# 10_header.net
KiCad netlist of a schematic drawn in Altium Designer
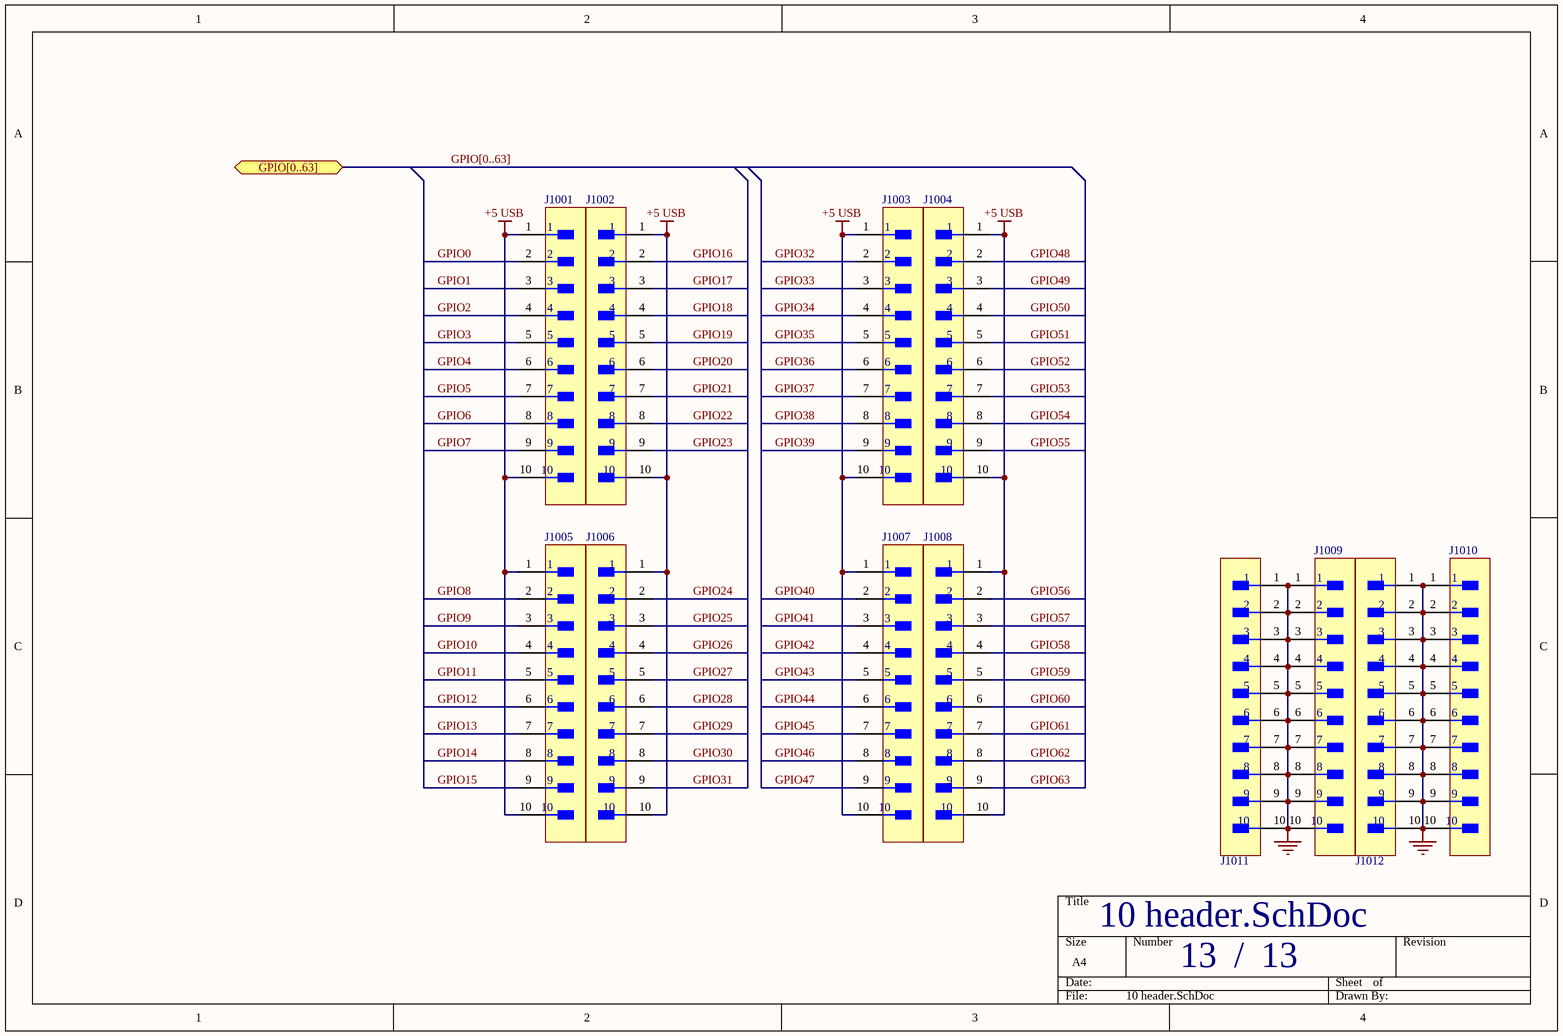
[diagram p0: 10 header.SchDoc]

(export (version "E")
  (design (tool "Eeschema 10.0.6"))
  (components
    (comp (ref "J1001")
      (value "TSW-110-07-T-S")
      (footprint "FP-TSW-110-07-T-S-MFG")
      (description "TSW-110-07-T-S TSW - Samtec 2.54mm Pin Header 10.92mm Overall Pin Length (07) (mcv)(TO22)")
      (libsource (lib "Altium Content Vault") (part "TSW-110-07-T-S"))
    )
    (comp (ref "J1002")
      (value "TSW-110-07-T-S")
      (footprint "FP-TSW-110-07-T-S-MFG")
      (description "TSW-110-07-T-S TSW - Samtec 2.54mm Pin Header 10.92mm Overall Pin Length (07) (mcv)(TO22)")
      (libsource (lib "") (part "TSW-110-07-T-S_1"))
    )
    (comp (ref "J1003")
      (value "TSW-110-07-T-S")
      (footprint "FP-TSW-110-07-T-S-MFG")
      (description "TSW-110-07-T-S TSW - Samtec 2.54mm Pin Header 10.92mm Overall Pin Length (07) (mcv)(TO22)")
      (libsource (lib "Altium Content Vault") (part "TSW-110-07-T-S"))
    )
    (comp (ref "J1004")
      (value "TSW-110-07-T-S")
      (footprint "FP-TSW-110-07-T-S-MFG")
      (description "TSW-110-07-T-S TSW - Samtec 2.54mm Pin Header 10.92mm Overall Pin Length (07) (mcv)(TO22)")
      (libsource (lib "") (part "TSW-110-07-T-S_1"))
    )
    (comp (ref "J1005")
      (value "TSW-110-07-T-S")
      (footprint "FP-TSW-110-07-T-S-MFG")
      (description "TSW-110-07-T-S TSW - Samtec 2.54mm Pin Header 10.92mm Overall Pin Length (07) (mcv)(TO22)")
      (libsource (lib "Altium Content Vault") (part "TSW-110-07-T-S"))
    )
    (comp (ref "J1006")
      (value "TSW-110-07-T-S")
      (footprint "FP-TSW-110-07-T-S-MFG")
      (description "TSW-110-07-T-S TSW - Samtec 2.54mm Pin Header 10.92mm Overall Pin Length (07) (mcv)(TO22)")
      (libsource (lib "") (part "TSW-110-07-T-S_1"))
    )
    (comp (ref "J1007")
      (value "TSW-110-07-T-S")
      (footprint "FP-TSW-110-07-T-S-MFG")
      (description "TSW-110-07-T-S TSW - Samtec 2.54mm Pin Header 10.92mm Overall Pin Length (07) (mcv)(TO22)")
      (libsource (lib "Altium Content Vault") (part "TSW-110-07-T-S"))
    )
    (comp (ref "J1008")
      (value "TSW-110-07-T-S")
      (footprint "FP-TSW-110-07-T-S-MFG")
      (description "TSW-110-07-T-S TSW - Samtec 2.54mm Pin Header 10.92mm Overall Pin Length (07) (mcv)(TO22)")
      (libsource (lib "") (part "TSW-110-07-T-S_1"))
    )
    (comp (ref "J1009")
      (value "TSW-110-07-T-S")
      (footprint "FP-TSW-110-07-T-S-MFG")
      (description "TSW-110-07-T-S TSW - Samtec 2.54mm Pin Header 10.92mm Overall Pin Length (07) (mcv)(TO22)")
      (libsource (lib "Altium Content Vault") (part "TSW-110-07-T-S"))
    )
    (comp (ref "J1010")
      (value "TSW-110-07-T-S")
      (footprint "FP-TSW-110-07-T-S-MFG")
      (description "TSW-110-07-T-S TSW - Samtec 2.54mm Pin Header 10.92mm Overall Pin Length (07) (mcv)(TO22)")
      (libsource (lib "Altium Content Vault") (part "TSW-110-07-T-S"))
    )
    (comp (ref "J1011")
      (value "TSW-110-07-T-S")
      (footprint "FP-TSW-110-07-T-S-MFG")
      (description "TSW-110-07-T-S TSW - Samtec 2.54mm Pin Header 10.92mm Overall Pin Length (07) (mcv)(TO22)")
      (libsource (lib "") (part "TSW-110-07-T-S_1"))
    )
    (comp (ref "J1012")
      (value "TSW-110-07-T-S")
      (footprint "FP-TSW-110-07-T-S-MFG")
      (description "TSW-110-07-T-S TSW - Samtec 2.54mm Pin Header 10.92mm Overall Pin Length (07) (mcv)(TO22)")
      (libsource (lib "") (part "TSW-110-07-T-S_1"))
    )
  )
  (nets
    (net (code "1") (name "+5 USB") (class "Default")
      (node (ref "J1001") (pin "1") (pinfunction "1_1") (pintype "passive"))
      (node (ref "J1001") (pin "10") (pinfunction "10_10") (pintype "passive"))
      (node (ref "J1002") (pin "1") (pinfunction "1_1") (pintype "passive"))
      (node (ref "J1002") (pin "10") (pinfunction "10_10") (pintype "passive"))
      (node (ref "J1003") (pin "1") (pinfunction "1_1") (pintype "passive"))
      (node (ref "J1003") (pin "10") (pinfunction "10_10") (pintype "passive"))
      (node (ref "J1004") (pin "1") (pinfunction "1_1") (pintype "passive"))
      (node (ref "J1004") (pin "10") (pinfunction "10_10") (pintype "passive"))
      (node (ref "J1005") (pin "1") (pinfunction "1_1") (pintype "passive"))
      (node (ref "J1005") (pin "10") (pinfunction "10_10") (pintype "passive"))
      (node (ref "J1006") (pin "1") (pinfunction "1_1") (pintype "passive"))
      (node (ref "J1006") (pin "10") (pinfunction "10_10") (pintype "passive"))
      (node (ref "J1007") (pin "1") (pinfunction "1_1") (pintype "passive"))
      (node (ref "J1007") (pin "10") (pinfunction "10_10") (pintype "passive"))
      (node (ref "J1008") (pin "1") (pinfunction "1_1") (pintype "passive"))
      (node (ref "J1008") (pin "10") (pinfunction "10_10") (pintype "passive"))
    )
    (net (code "2") (name "/GPIO0") (class "Default")
      (node (ref "J1001") (pin "2") (pinfunction "2_2") (pintype "passive"))
    )
    (net (code "3") (name "/GPIO1") (class "Default")
      (node (ref "J1001") (pin "3") (pinfunction "3_3") (pintype "passive"))
    )
    (net (code "4") (name "/GPIO2") (class "Default")
      (node (ref "J1001") (pin "4") (pinfunction "4_4") (pintype "passive"))
    )
    (net (code "5") (name "/GPIO3") (class "Default")
      (node (ref "J1001") (pin "5") (pinfunction "5_5") (pintype "passive"))
    )
    (net (code "6") (name "/GPIO4") (class "Default")
      (node (ref "J1001") (pin "6") (pinfunction "6_6") (pintype "passive"))
    )
    (net (code "7") (name "/GPIO5") (class "Default")
      (node (ref "J1001") (pin "7") (pinfunction "7_7") (pintype "passive"))
    )
    (net (code "8") (name "/GPIO6") (class "Default")
      (node (ref "J1001") (pin "8") (pinfunction "8_8") (pintype "passive"))
    )
    (net (code "9") (name "/GPIO7") (class "Default")
      (node (ref "J1001") (pin "9") (pinfunction "9_9") (pintype "passive"))
    )
    (net (code "10") (name "/GPIO8") (class "Default")
      (node (ref "J1005") (pin "2") (pinfunction "2_2") (pintype "passive"))
    )
    (net (code "11") (name "/GPIO9") (class "Default")
      (node (ref "J1005") (pin "3") (pinfunction "3_3") (pintype "passive"))
    )
    (net (code "12") (name "/GPIO10") (class "Default")
      (node (ref "J1005") (pin "4") (pinfunction "4_4") (pintype "passive"))
    )
    (net (code "13") (name "/GPIO11") (class "Default")
      (node (ref "J1005") (pin "5") (pinfunction "5_5") (pintype "passive"))
    )
    (net (code "14") (name "/GPIO12") (class "Default")
      (node (ref "J1005") (pin "6") (pinfunction "6_6") (pintype "passive"))
    )
    (net (code "15") (name "/GPIO13") (class "Default")
      (node (ref "J1005") (pin "7") (pinfunction "7_7") (pintype "passive"))
    )
    (net (code "16") (name "/GPIO14") (class "Default")
      (node (ref "J1005") (pin "8") (pinfunction "8_8") (pintype "passive"))
    )
    (net (code "17") (name "/GPIO15") (class "Default")
      (node (ref "J1005") (pin "9") (pinfunction "9_9") (pintype "passive"))
    )
    (net (code "18") (name "/GPIO16") (class "Default")
      (node (ref "J1002") (pin "2") (pinfunction "2_2") (pintype "passive"))
    )
    (net (code "19") (name "/GPIO17") (class "Default")
      (node (ref "J1002") (pin "3") (pinfunction "3_3") (pintype "passive"))
    )
    (net (code "20") (name "/GPIO18") (class "Default")
      (node (ref "J1002") (pin "4") (pinfunction "4_4") (pintype "passive"))
    )
    (net (code "21") (name "/GPIO19") (class "Default")
      (node (ref "J1002") (pin "5") (pinfunction "5_5") (pintype "passive"))
    )
    (net (code "22") (name "/GPIO20") (class "Default")
      (node (ref "J1002") (pin "6") (pinfunction "6_6") (pintype "passive"))
    )
    (net (code "23") (name "/GPIO21") (class "Default")
      (node (ref "J1002") (pin "7") (pinfunction "7_7") (pintype "passive"))
    )
    (net (code "24") (name "/GPIO22") (class "Default")
      (node (ref "J1002") (pin "8") (pinfunction "8_8") (pintype "passive"))
    )
    (net (code "25") (name "/GPIO23") (class "Default")
      (node (ref "J1002") (pin "9") (pinfunction "9_9") (pintype "passive"))
    )
    (net (code "26") (name "/GPIO24") (class "Default")
      (node (ref "J1006") (pin "2") (pinfunction "2_2") (pintype "passive"))
    )
    (net (code "27") (name "/GPIO25") (class "Default")
      (node (ref "J1006") (pin "3") (pinfunction "3_3") (pintype "passive"))
    )
    (net (code "28") (name "/GPIO26") (class "Default")
      (node (ref "J1006") (pin "4") (pinfunction "4_4") (pintype "passive"))
    )
    (net (code "29") (name "/GPIO27") (class "Default")
      (node (ref "J1006") (pin "5") (pinfunction "5_5") (pintype "passive"))
    )
    (net (code "30") (name "/GPIO28") (class "Default")
      (node (ref "J1006") (pin "6") (pinfunction "6_6") (pintype "passive"))
    )
    (net (code "31") (name "/GPIO29") (class "Default")
      (node (ref "J1006") (pin "7") (pinfunction "7_7") (pintype "passive"))
    )
    (net (code "32") (name "/GPIO30") (class "Default")
      (node (ref "J1006") (pin "8") (pinfunction "8_8") (pintype "passive"))
    )
    (net (code "33") (name "/GPIO31") (class "Default")
      (node (ref "J1006") (pin "9") (pinfunction "9_9") (pintype "passive"))
    )
    (net (code "34") (name "/GPIO32") (class "Default")
      (node (ref "J1003") (pin "2") (pinfunction "2_2") (pintype "passive"))
    )
    (net (code "35") (name "/GPIO33") (class "Default")
      (node (ref "J1003") (pin "3") (pinfunction "3_3") (pintype "passive"))
    )
    (net (code "36") (name "/GPIO34") (class "Default")
      (node (ref "J1003") (pin "4") (pinfunction "4_4") (pintype "passive"))
    )
    (net (code "37") (name "/GPIO35") (class "Default")
      (node (ref "J1003") (pin "5") (pinfunction "5_5") (pintype "passive"))
    )
    (net (code "38") (name "/GPIO36") (class "Default")
      (node (ref "J1003") (pin "6") (pinfunction "6_6") (pintype "passive"))
    )
    (net (code "39") (name "/GPIO37") (class "Default")
      (node (ref "J1003") (pin "7") (pinfunction "7_7") (pintype "passive"))
    )
    (net (code "40") (name "/GPIO38") (class "Default")
      (node (ref "J1003") (pin "8") (pinfunction "8_8") (pintype "passive"))
    )
    (net (code "41") (name "/GPIO39") (class "Default")
      (node (ref "J1003") (pin "9") (pinfunction "9_9") (pintype "passive"))
    )
    (net (code "42") (name "/GPIO40") (class "Default")
      (node (ref "J1007") (pin "2") (pinfunction "2_2") (pintype "passive"))
    )
    (net (code "43") (name "/GPIO41") (class "Default")
      (node (ref "J1007") (pin "3") (pinfunction "3_3") (pintype "passive"))
    )
    (net (code "44") (name "/GPIO42") (class "Default")
      (node (ref "J1007") (pin "4") (pinfunction "4_4") (pintype "passive"))
    )
    (net (code "45") (name "/GPIO43") (class "Default")
      (node (ref "J1007") (pin "5") (pinfunction "5_5") (pintype "passive"))
    )
    (net (code "46") (name "/GPIO44") (class "Default")
      (node (ref "J1007") (pin "6") (pinfunction "6_6") (pintype "passive"))
    )
    (net (code "47") (name "/GPIO45") (class "Default")
      (node (ref "J1007") (pin "7") (pinfunction "7_7") (pintype "passive"))
    )
    (net (code "48") (name "/GPIO46") (class "Default")
      (node (ref "J1007") (pin "8") (pinfunction "8_8") (pintype "passive"))
    )
    (net (code "49") (name "/GPIO47") (class "Default")
      (node (ref "J1007") (pin "9") (pinfunction "9_9") (pintype "passive"))
    )
    (net (code "50") (name "/GPIO48") (class "Default")
      (node (ref "J1004") (pin "2") (pinfunction "2_2") (pintype "passive"))
    )
    (net (code "51") (name "/GPIO49") (class "Default")
      (node (ref "J1004") (pin "3") (pinfunction "3_3") (pintype "passive"))
    )
    (net (code "52") (name "/GPIO50") (class "Default")
      (node (ref "J1004") (pin "4") (pinfunction "4_4") (pintype "passive"))
    )
    (net (code "53") (name "/GPIO51") (class "Default")
      (node (ref "J1004") (pin "5") (pinfunction "5_5") (pintype "passive"))
    )
    (net (code "54") (name "/GPIO52") (class "Default")
      (node (ref "J1004") (pin "6") (pinfunction "6_6") (pintype "passive"))
    )
    (net (code "55") (name "/GPIO53") (class "Default")
      (node (ref "J1004") (pin "7") (pinfunction "7_7") (pintype "passive"))
    )
    (net (code "56") (name "/GPIO54") (class "Default")
      (node (ref "J1004") (pin "8") (pinfunction "8_8") (pintype "passive"))
    )
    (net (code "57") (name "/GPIO55") (class "Default")
      (node (ref "J1004") (pin "9") (pinfunction "9_9") (pintype "passive"))
    )
    (net (code "58") (name "/GPIO56") (class "Default")
      (node (ref "J1008") (pin "2") (pinfunction "2_2") (pintype "passive"))
    )
    (net (code "59") (name "/GPIO57") (class "Default")
      (node (ref "J1008") (pin "3") (pinfunction "3_3") (pintype "passive"))
    )
    (net (code "60") (name "/GPIO58") (class "Default")
      (node (ref "J1008") (pin "4") (pinfunction "4_4") (pintype "passive"))
    )
    (net (code "61") (name "/GPIO59") (class "Default")
      (node (ref "J1008") (pin "5") (pinfunction "5_5") (pintype "passive"))
    )
    (net (code "62") (name "/GPIO60") (class "Default")
      (node (ref "J1008") (pin "6") (pinfunction "6_6") (pintype "passive"))
    )
    (net (code "63") (name "/GPIO61") (class "Default")
      (node (ref "J1008") (pin "7") (pinfunction "7_7") (pintype "passive"))
    )
    (net (code "64") (name "/GPIO62") (class "Default")
      (node (ref "J1008") (pin "8") (pinfunction "8_8") (pintype "passive"))
    )
    (net (code "65") (name "/GPIO63") (class "Default")
      (node (ref "J1008") (pin "9") (pinfunction "9_9") (pintype "passive"))
    )
    (net (code "67") (name "GND") (class "Default")
      (node (ref "J1009") (pin "1") (pinfunction "1_1") (pintype "passive"))
      (node (ref "J1009") (pin "10") (pinfunction "10_10") (pintype "passive"))
      (node (ref "J1009") (pin "2") (pinfunction "2_2") (pintype "passive"))
      (node (ref "J1009") (pin "3") (pinfunction "3_3") (pintype "passive"))
      (node (ref "J1009") (pin "4") (pinfunction "4_4") (pintype "passive"))
      (node (ref "J1009") (pin "5") (pinfunction "5_5") (pintype "passive"))
      (node (ref "J1009") (pin "6") (pinfunction "6_6") (pintype "passive"))
      (node (ref "J1009") (pin "7") (pinfunction "7_7") (pintype "passive"))
      (node (ref "J1009") (pin "8") (pinfunction "8_8") (pintype "passive"))
      (node (ref "J1009") (pin "9") (pinfunction "9_9") (pintype "passive"))
      (node (ref "J1010") (pin "1") (pinfunction "1_1") (pintype "passive"))
      (node (ref "J1010") (pin "10") (pinfunction "10_10") (pintype "passive"))
      (node (ref "J1010") (pin "2") (pinfunction "2_2") (pintype "passive"))
      (node (ref "J1010") (pin "3") (pinfunction "3_3") (pintype "passive"))
      (node (ref "J1010") (pin "4") (pinfunction "4_4") (pintype "passive"))
      (node (ref "J1010") (pin "5") (pinfunction "5_5") (pintype "passive"))
      (node (ref "J1010") (pin "6") (pinfunction "6_6") (pintype "passive"))
      (node (ref "J1010") (pin "7") (pinfunction "7_7") (pintype "passive"))
      (node (ref "J1010") (pin "8") (pinfunction "8_8") (pintype "passive"))
      (node (ref "J1010") (pin "9") (pinfunction "9_9") (pintype "passive"))
      (node (ref "J1011") (pin "1") (pinfunction "1_1") (pintype "passive"))
      (node (ref "J1011") (pin "10") (pinfunction "10_10") (pintype "passive"))
      (node (ref "J1011") (pin "2") (pinfunction "2_2") (pintype "passive"))
      (node (ref "J1011") (pin "3") (pinfunction "3_3") (pintype "passive"))
      (node (ref "J1011") (pin "4") (pinfunction "4_4") (pintype "passive"))
      (node (ref "J1011") (pin "5") (pinfunction "5_5") (pintype "passive"))
      (node (ref "J1011") (pin "6") (pinfunction "6_6") (pintype "passive"))
      (node (ref "J1011") (pin "7") (pinfunction "7_7") (pintype "passive"))
      (node (ref "J1011") (pin "8") (pinfunction "8_8") (pintype "passive"))
      (node (ref "J1011") (pin "9") (pinfunction "9_9") (pintype "passive"))
      (node (ref "J1012") (pin "1") (pinfunction "1_1") (pintype "passive"))
      (node (ref "J1012") (pin "10") (pinfunction "10_10") (pintype "passive"))
      (node (ref "J1012") (pin "2") (pinfunction "2_2") (pintype "passive"))
      (node (ref "J1012") (pin "3") (pinfunction "3_3") (pintype "passive"))
      (node (ref "J1012") (pin "4") (pinfunction "4_4") (pintype "passive"))
      (node (ref "J1012") (pin "5") (pinfunction "5_5") (pintype "passive"))
      (node (ref "J1012") (pin "6") (pinfunction "6_6") (pintype "passive"))
      (node (ref "J1012") (pin "7") (pinfunction "7_7") (pintype "passive"))
      (node (ref "J1012") (pin "8") (pinfunction "8_8") (pintype "passive"))
      (node (ref "J1012") (pin "9") (pinfunction "9_9") (pintype "passive"))
    )
  )
)
